# SolarPanel__X.net
KiCad netlist of a schematic drawn in Altium Designer
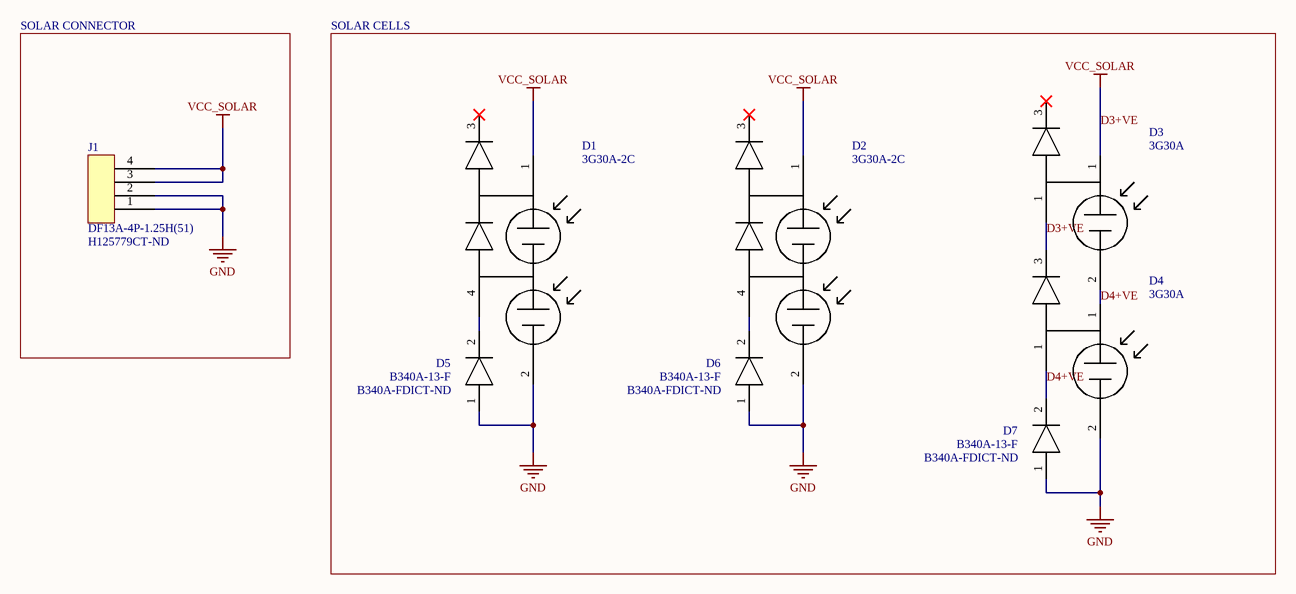
[diagram p0: SolarPanel_+X.SchDoc]

(export (version "E")
  (design (tool "Eeschema 10.0.6"))
  (components
    (comp (ref "D1")
      (value "3G30A-2C")
      (footprint "3G30A_2C")
      (description "Solar cell x2")
      (libsource (lib "heron-general") (part "3G30A-2C"))
    )
    (comp (ref "D2")
      (value "3G30A-2C")
      (footprint "3G30A_2C")
      (description "Solar cell x2")
      (libsource (lib "heron-general") (part "3G30A-2C"))
    )
    (comp (ref "D3")
      (value "3G30A")
      (footprint "3G30A")
      (description "Single solar cell")
      (libsource (lib "heron-general") (part "3G30A"))
    )
    (comp (ref "D4")
      (value "3G30A")
      (footprint "3G30A")
      (description "Single solar cell")
      (libsource (lib "heron-general") (part "3G30A"))
    )
    (comp (ref "D5")
      (value "B340A-13-F")
      (footprint "B340A-13-F")
      (description "Schottky diode")
      (fields (field (name "SUPPLIER PART NUMBER 1") "B340A-FDICT-ND"))
      (libsource (lib "heron-general") (part "B340A-13-F"))
    )
    (comp (ref "D6")
      (value "B340A-13-F")
      (footprint "B340A-13-F")
      (description "Schottky diode")
      (fields (field (name "SUPPLIER PART NUMBER 1") "B340A-FDICT-ND"))
      (libsource (lib "heron-general") (part "B340A-13-F"))
    )
    (comp (ref "D7")
      (value "B340A-13-F")
      (footprint "B340A-13-F")
      (description "Schottky diode")
      (fields (field (name "SUPPLIER PART NUMBER 1") "B340A-FDICT-ND"))
      (libsource (lib "heron-general") (part "B340A-13-F"))
    )
    (comp (ref "J1")
      (value "DF13A-4P-1.25H(51)")
      (footprint "DF13A-4P-1.25H(51)")
      (description "4 pos DF13 right angle surface mount connector")
      (fields (field (name "SUPPLIER PART NUMBER 1") "H125779CT-ND"))
      (libsource (lib "heron-general") (part "DF13A-4P-1.25H(51)"))
    )
  )
  (nets
    (net (code "1") (name "/D4+VE") (class "Default")
      (node (ref "D3") (pin "2") (pintype "passive"))
      (node (ref "D4") (pin "1") (pintype "passive"))
      (node (ref "D7") (pin "2") (pintype "passive"))
    )
    (net (code "2") (name "GND") (class "Default")
      (node (ref "D1") (pin "2") (pintype "passive"))
      (node (ref "D2") (pin "2") (pintype "passive"))
      (node (ref "D4") (pin "2") (pintype "passive"))
      (node (ref "D5") (pin "1") (pintype "passive"))
      (node (ref "D6") (pin "1") (pintype "passive"))
      (node (ref "D7") (pin "1") (pintype "passive"))
      (node (ref "J1") (pin "1") (pintype "passive"))
      (node (ref "J1") (pin "2") (pintype "passive"))
    )
    (net (code "3") (name "Net-(D1-Pad4)") (class "Default")
      (node (ref "D1") (pin "4") (pintype "passive"))
      (node (ref "D5") (pin "2") (pintype "passive"))
    )
    (net (code "4") (name "Net-(D2-Pad4)") (class "Default")
      (node (ref "D2") (pin "4") (pintype "passive"))
      (node (ref "D6") (pin "2") (pintype "passive"))
    )
    (net (code "5") (name "VCC_SOLAR") (class "Default")
      (node (ref "D1") (pin "1") (pintype "passive"))
      (node (ref "D2") (pin "1") (pintype "passive"))
      (node (ref "D3") (pin "1") (pintype "passive"))
      (node (ref "D4") (pin "3") (pintype "passive"))
      (node (ref "J1") (pin "3") (pintype "passive"))
      (node (ref "J1") (pin "4") (pintype "passive"))
    )
    (net (code "6") (name "unconnected-(D1-Pad3)") (class "Default")
      (node (ref "D1") (pin "3") (pintype "passive+no_connect"))
    )
    (net (code "7") (name "unconnected-(D2-Pad3)") (class "Default")
      (node (ref "D2") (pin "3") (pintype "passive+no_connect"))
    )
    (net (code "8") (name "unconnected-(D3-Pad3)") (class "Default")
      (node (ref "D3") (pin "3") (pintype "passive+no_connect"))
    )
  )
)
